# 15_LMS2_RF1_Misc.net
KiCad netlist of a schematic drawn in Altium Designer
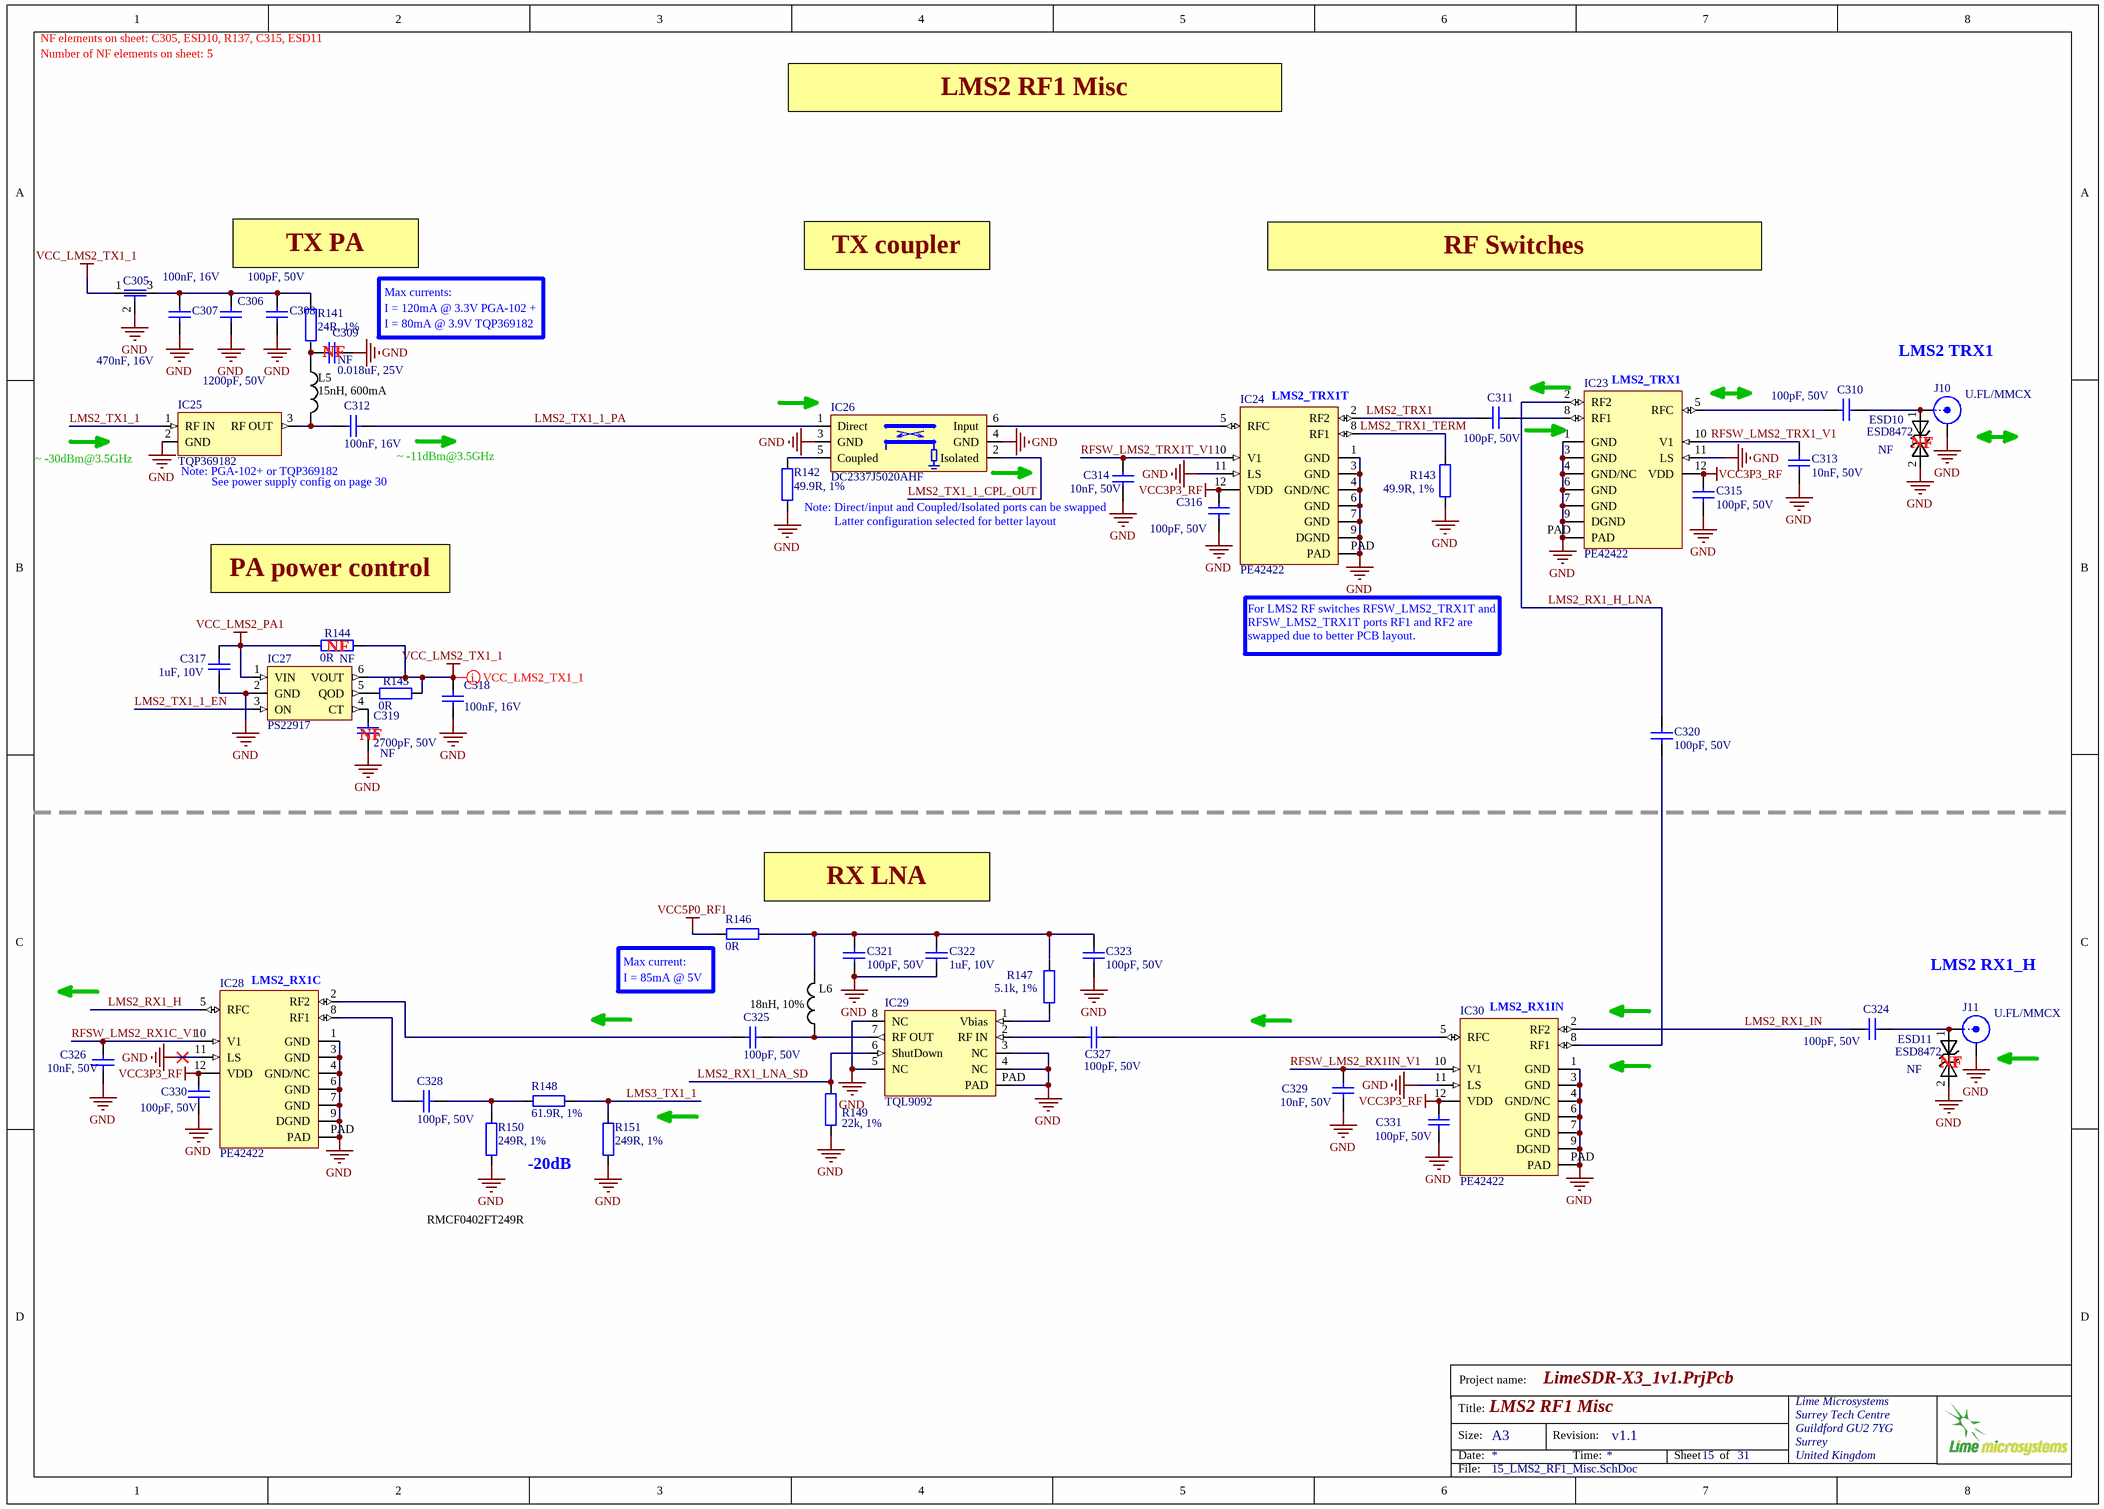
[diagram p0: 15_LMS2_RF1_Misc.SchDoc]

(export (version "E")
  (design (tool "Eeschema 10.0.6"))
  (components
    (comp (ref "C305")
      (value "470nF, 16V")
      (footprint "CAP0805_FEEDTHROUGH")
      (fields
        (field (name "MANUFACTURER") "Murata")
        (field (name "TOLERANCE") "20%")
        (field (name "VOLTAGE") "16V")
      )
      (libsource (lib "LimeMicroAltiumLib_schLib_r01") (part "Cap_feed_through"))
    )
    (comp (ref "C306")
      (value "1200pF, 50V")
      (footprint "CAP0402")
      (fields (field (name "MANUFACTURER") "Kemet") (field (name "TOLERANCE") "±5%"))
      (libsource (lib "") (part "Cap_0402_12"))
    )
    (comp (ref "C307")
      (value "100nF, 16V")
      (footprint "CAP0402")
      (fields (field (name "MANUFACTURER") "Murata Electronics") (field (name "TOLERANCE") "10 %"))
      (libsource (lib "") (part "Cap_0402_10"))
    )
    (comp (ref "C308")
      (value "100pF, 50V")
      (footprint "CAP0402")
      (fields (field (name "TOLERANCE") "±5%") (field (name "MANUFACTURER") "Yageo"))
      (libsource (lib "") (part "Cap_0402_10"))
    )
    (comp (ref "C309")
      (value "0.018uF, 25V")
      (footprint "CAP0402")
      (fields
        (field (name "ASSEMBLY INFO") "NF")
        (field (name "MANUFACTURER") "Yageo")
        (field (name "TOLERANCE") "10%")
      )
      (libsource (lib "") (part "Cap_0402_5"))
    )
    (comp (ref "C310")
      (value "100pF, 50V")
      (footprint "CAP0402")
      (fields (field (name "TOLERANCE") "±5%") (field (name "MANUFACTURER") "Yageo"))
      (libsource (lib "") (part "Cap_0402_3"))
    )
    (comp (ref "C311")
      (value "100pF, 50V")
      (footprint "CAP0402")
      (fields (field (name "TOLERANCE") "±5%") (field (name "MANUFACTURER") "Yageo"))
      (libsource (lib "") (part "Cap_0402_3"))
    )
    (comp (ref "C312")
      (value "100nF, 16V")
      (footprint "CAP0402")
      (fields (field (name "MANUFACTURER") "Murata Electronics") (field (name "TOLERANCE") "10 %"))
      (libsource (lib "") (part "Cap_0402_1"))
    )
    (comp (ref "C313")
      (value "10nF, 50V")
      (footprint "CAP0402")
      (fields
        (field (name "MANUFACTURER") "Murata Electronics North America")
        (field (name "TOLERANCE") "±10%")
      )
      (libsource (lib "") (part "Cap_0402_7"))
    )
    (comp (ref "C314")
      (value "10nF, 50V")
      (footprint "CAP0402")
      (fields
        (field (name "MANUFACTURER") "Murata Electronics North America")
        (field (name "TOLERANCE") "±10%")
      )
      (libsource (lib "") (part "Cap_0402_7"))
    )
    (comp (ref "C315")
      (value "100pF, 50V")
      (footprint "CAP0402")
      (fields (field (name "TOLERANCE") "±5%") (field (name "MANUFACTURER") "Yageo"))
      (libsource (lib "LimeMicroAltiumLib_schLib") (part "Cap_0402"))
    )
    (comp (ref "C316")
      (value "100pF, 50V")
      (footprint "CAP0402")
      (fields (field (name "TOLERANCE") "±5%") (field (name "MANUFACTURER") "Yageo"))
      (libsource (lib "LimeMicroAltiumLib_schLib") (part "Cap_0402"))
    )
    (comp (ref "C317")
      (value "1uF, 10V")
      (footprint "CAP0402")
      (fields (field (name "MANUFACTURER") "TDK"))
      (libsource (lib "") (part "Cap_0402_2"))
    )
    (comp (ref "C318")
      (value "100nF, 16V")
      (footprint "CAP0402")
      (fields (field (name "MANUFACTURER") "Murata Electronics") (field (name "TOLERANCE") "10 %"))
      (libsource (lib "") (part "Cap_0402_2"))
    )
    (comp (ref "C319")
      (value "2700pF, 50V")
      (footprint "CAP0402")
      (fields
        (field (name "ASSEMBLY INFO") "NF")
        (field (name "TOLERANCE") "±10%")
        (field (name "MANUFACTURER") "Murata Electronics North America")
      )
      (libsource (lib "") (part "Cap_0402_10"))
    )
    (comp (ref "C320")
      (value "100pF, 50V")
      (footprint "CAP0402")
      (fields (field (name "TOLERANCE") "±5%") (field (name "MANUFACTURER") "Yageo"))
      (libsource (lib "") (part "Cap_0402_3"))
    )
    (comp (ref "C321")
      (value "100pF, 50V")
      (footprint "CAP0402")
      (fields (field (name "TOLERANCE") "±5%") (field (name "MANUFACTURER") "Yageo"))
      (libsource (lib "") (part "Cap_0402_8"))
    )
    (comp (ref "C322")
      (value "1uF, 10V")
      (footprint "CAP0402")
      (fields (field (name "MANUFACTURER") "TDK"))
      (libsource (lib "") (part "Cap_0402_11"))
    )
    (comp (ref "C323")
      (value "100pF, 50V")
      (footprint "CAP0402")
      (fields (field (name "TOLERANCE") "±5%") (field (name "MANUFACTURER") "Yageo"))
      (libsource (lib "") (part "Cap_0402_8"))
    )
    (comp (ref "C324")
      (value "100pF, 50V")
      (footprint "CAP0402")
      (fields (field (name "TOLERANCE") "±5%") (field (name "MANUFACTURER") "Yageo"))
      (libsource (lib "") (part "Cap_0402_3"))
    )
    (comp (ref "C325")
      (value "100pF, 50V")
      (footprint "CAP0402")
      (fields (field (name "TOLERANCE") "±5%") (field (name "MANUFACTURER") "Yageo"))
      (libsource (lib "") (part "Cap_0402_2"))
    )
    (comp (ref "C326")
      (value "10nF, 50V")
      (footprint "CAP0402")
      (fields
        (field (name "MANUFACTURER") "Murata Electronics North America")
        (field (name "TOLERANCE") "±10%")
      )
      (libsource (lib "") (part "Cap_0402_4"))
    )
    (comp (ref "C327")
      (value "100pF, 50V")
      (footprint "CAP0402")
      (fields (field (name "TOLERANCE") "±5%") (field (name "MANUFACTURER") "Yageo"))
      (libsource (lib "") (part "Cap_0402_6"))
    )
    (comp (ref "C328")
      (value "100pF, 50V")
      (footprint "CAP0402")
      (fields (field (name "TOLERANCE") "±5%") (field (name "MANUFACTURER") "Yageo"))
      (libsource (lib "") (part "Cap_0402_3"))
    )
    (comp (ref "C329")
      (value "10nF, 50V")
      (footprint "CAP0402")
      (fields
        (field (name "MANUFACTURER") "Murata Electronics North America")
        (field (name "TOLERANCE") "±10%")
      )
      (libsource (lib "") (part "Cap_0402_5"))
    )
    (comp (ref "C330")
      (value "100pF, 50V")
      (footprint "CAP0402")
      (fields (field (name "TOLERANCE") "±5%") (field (name "MANUFACTURER") "Yageo"))
      (libsource (lib "") (part "Cap_0402_9"))
    )
    (comp (ref "C331")
      (value "100pF, 50V")
      (footprint "CAP0402")
      (fields (field (name "TOLERANCE") "±5%") (field (name "MANUFACTURER") "Yageo"))
      (libsource (lib "") (part "Cap_0402_1"))
    )
    (comp (ref "ESD10")
      (value "ESD8472")
      (footprint "ESD8472_X3DFN2")
      (fields (field (name "MANUFACTURER") "ON Semiconductor") (field (name "ASSEMBLY INFO") "NF"))
      (libsource (lib "LimeMicroAltiumLib_schLib") (part "ESD8472"))
    )
    (comp (ref "ESD11")
      (value "ESD8472")
      (footprint "ESD8472_X3DFN2")
      (fields (field (name "MANUFACTURER") "ON Semiconductor") (field (name "ASSEMBLY INFO") "NF"))
      (libsource (lib "") (part "ESD8472_1"))
    )
    (comp (ref "IC23")
      (value "PE42422")
      (footprint "PE42422_QFN12")
      (fields (field (name "MANUFACTURER") "Peregrine Semiconductor"))
      (libsource (lib "") (part "PE42422_3"))
    )
    (comp (ref "IC24")
      (value "PE42422")
      (footprint "PE42422_QFN12")
      (fields (field (name "MANUFACTURER") "Peregrine Semiconductor"))
      (libsource (lib "LimeMicroAltiumLib_schLib") (part "PE42422"))
    )
    (comp (ref "IC25")
      (value "TQP369182")
      (footprint "PGA-102+_SOT89")
      (fields (field (name "MANUFACTURER") "Qorvo"))
      (libsource (lib "LimeMicroAltiumLib_schLib_r01") (part "PGA-102+_PA"))
    )
    (comp (ref "IC26")
      (value "DC2337J5020AHF")
      (footprint "DC2337J5020AHF_ANAREN_COUPLER_0805")
      (fields (field (name "MANUFACTURER") "Anaren"))
      (libsource (lib "LimeMicroAltiumLib_schLib_r02") (part "DC2337J5020AHF_coupler"))
    )
    (comp (ref "IC27")
      (value "PS22917")
      (footprint "SOT23-6")
      (fields (field (name "MANUFACTURER") "Texas Instruments"))
      (libsource (lib "LimeMicroAltiumLib_schLib") (part "TPS22918"))
    )
    (comp (ref "IC28")
      (value "PE42422")
      (footprint "PE42422_QFN12")
      (fields (field (name "MANUFACTURER") "Peregrine Semiconductor"))
      (libsource (lib "") (part "PE42422_1"))
    )
    (comp (ref "IC29")
      (value "TQL9092")
      (footprint "TQL9092")
      (fields (field (name "MANUFACTURER") "Qorvo"))
      (libsource (lib "LimeMicroAltiumLib_schLib") (part "TQL9092"))
    )
    (comp (ref "IC30")
      (value "PE42422")
      (footprint "PE42422_QFN12")
      (fields (field (name "MANUFACTURER") "Peregrine Semiconductor"))
      (libsource (lib "") (part "PE42422_2"))
    )
    (comp (ref "J10")
      (value "U.FL/MMCX")
      (footprint "MMCX_UFL_conn_m")
      (description "CONN UMC RCPT STR 50 OHM SMD")
      (fields (field (name "MANUFACTURER") "Amphenol RF"))
      (libsource (lib "LimeMicroAltiumLib_schLib") (part "RF_IF_connector"))
    )
    (comp (ref "J11")
      (value "U.FL/MMCX")
      (footprint "MMCX_UFL_conn_m")
      (description "CONN UMC RCPT STR 50 OHM SMD")
      (fields (field (name "MANUFACTURER") "Amphenol RF"))
      (libsource (lib "LimeMicroAltiumLib_schLib") (part "RF_IF_connector"))
    )
    (comp (ref "L5")
      (value "15nH, 600mA")
      (footprint "RES0805")
      (fields (field (name "MANUFACTURER") "Bourns") (field (name "TOLERANCE") "5%"))
      (libsource (lib "LimeMicroAltiumLib_schLib") (part "Inductor_0603"))
    )
    (comp (ref "L6")
      (value "18nH, 10%")
      (footprint "RES0603")
      (fields (field (name "MANUFACTURER") "Pulse Electronics Network") (field (name "TOLERANCE") "±10%"))
      (libsource (lib "LimeMicroAltiumLib_schLib") (part "Inductor"))
    )
    (comp (ref "R141")
      (value "24R, 1%")
      (footprint "RES0402")
      (fields (field (name "MANUFACTURER") "Yageo") (field (name "TOLERANCE") "1%"))
      (libsource (lib "LimeFPGAboard_schLib") (part "Res_0402"))
    )
    (comp (ref "R142")
      (value "49.9R, 1%")
      (footprint "RES0402")
      (fields
        (field (name "TOLERANCE") "±1%")
        (field (name "MANUFACTURER") "Samsung Electro-Mechanics America, Inc.")
        (field (name "MANUFACTURER PART NUMBER") "RC1005F49R9CS")
      )
      (libsource (lib "LimeMicroAltiumLib_schLib") (part "Res_0402"))
    )
    (comp (ref "R143")
      (value "49.9R, 1%")
      (footprint "RES0402")
      (fields
        (field (name "TOLERANCE") "±1%")
        (field (name "MANUFACTURER") "Samsung Electro-Mechanics America, Inc.")
        (field (name "MANUFACTURER PART NUMBER") "RC1005F49R9CS")
      )
      (libsource (lib "LimeMicroAltiumLib_schLib") (part "Res_0402"))
    )
    (comp (ref "R144")
      (value "0R")
      (footprint "RES0402")
      (fields
        (field (name "ASSEMBLY INFO") "NF")
        (field (name "MANUFACTURER") "Yageo")
        (field (name "TOLERANCE") "Jumper")
      )
      (libsource (lib "") (part "Res_0402_1"))
    )
    (comp (ref "R145")
      (value "0R")
      (footprint "RES0402")
      (fields (field (name "MANUFACTURER") "Yageo") (field (name "TOLERANCE") "Jumper"))
      (libsource (lib "") (part "Res_0402_1"))
    )
    (comp (ref "R146")
      (value "0R")
      (footprint "RES0402")
      (fields (field (name "MANUFACTURER") "Yageo") (field (name "TOLERANCE") "Jumper"))
      (libsource (lib "LimeMicroAltiumLib_schLib") (part "Res_0402"))
    )
    (comp (ref "R147")
      (value "5.1k, 1%")
      (footprint "RES0603")
      (fields (field (name "MANUFACTURER") "Stackpole Electronics") (field (name "TOLERANCE") "1%"))
      (libsource (lib "LimeMicroAltiumLib_schLib") (part "Res_0603"))
    )
    (comp (ref "R148")
      (value "61.9R, 1%")
      (footprint "RES0402")
      (fields (field (name "MANUFACTURER") "Yageo") (field (name "TOLERANCE") "1%"))
      (libsource (lib "") (part "Res_0402_1"))
    )
    (comp (ref "R149")
      (value "22k, 1%")
      (footprint "RES0402")
      (fields (field (name "MANUFACTURER") "Yageo") (field (name "TOLERANCE") "±1%"))
      (libsource (lib "") (part "Res_0402_1"))
    )
    (comp (ref "R150")
      (value "249R, 1%")
      (footprint "RES0402")
      (fields (field (name "MANUFACTURER") "Stackpole Electronics Inc") (field (name "TOLERANCE") "±1%"))
      (libsource (lib "") (part "Res_0402_1"))
    )
    (comp (ref "R151")
      (value "249R, 1%")
      (footprint "RES0402")
      (fields (field (name "MANUFACTURER") "Stackpole Electronics Inc") (field (name "TOLERANCE") "±1%"))
      (libsource (lib "") (part "Res_0402_1"))
    )
  )
  (nets
    (net (code "1") (name "/LMS2_RX1_H") (class "Default")
      (node (ref "IC28") (pin "5") (pinfunction "RFC_5") (pintype "bidirectional"))
    )
    (net (code "2") (name "/LMS2_RX1_H_LNA") (class "Default")
      (node (ref "C320") (pin "2") (pinfunction "2_2") (pintype "passive"))
      (node (ref "IC23") (pin "2") (pinfunction "RF2_2") (pintype "bidirectional"))
    )
    (net (code "3") (name "/LMS2_RX1_IN") (class "Default")
      (node (ref "C324") (pin "1") (pinfunction "1_1") (pintype "passive"))
      (node (ref "IC30") (pin "2") (pinfunction "RF2_2") (pintype "bidirectional"))
    )
    (net (code "4") (name "/LMS2_RX1_LNA_SD") (class "Default")
      (node (ref "IC29") (pin "6") (pinfunction "ShutDown_6") (pintype "input"))
      (node (ref "R149") (pin "2") (pinfunction "2_2") (pintype "passive"))
    )
    (net (code "5") (name "/LMS2_TRX1") (class "Default")
      (node (ref "C311") (pin "1") (pinfunction "1_1") (pintype "passive"))
      (node (ref "IC24") (pin "2") (pinfunction "RF2_2") (pintype "bidirectional"))
    )
    (net (code "6") (name "/LMS2_TRX1_TERM") (class "Default")
      (node (ref "IC24") (pin "8") (pinfunction "RF1_8") (pintype "bidirectional"))
      (node (ref "R143") (pin "1") (pinfunction "1_1") (pintype "passive"))
    )
    (net (code "7") (name "/LMS2_TX1_1") (class "Default")
      (node (ref "IC25") (pin "1") (pinfunction "RF_IN_1") (pintype "input"))
    )
    (net (code "8") (name "/LMS2_TX1_1_CPL_OUT") (class "Default")
      (node (ref "IC26") (pin "2") (pinfunction "Isolated_2") (pintype "passive"))
    )
    (net (code "9") (name "/LMS2_TX1_1_EN") (class "Default")
      (node (ref "IC27") (pin "3") (pinfunction "ON_3") (pintype "input"))
    )
    (net (code "10") (name "/LMS2_TX1_1_PA") (class "Default")
      (node (ref "C312") (pin "1") (pinfunction "1_1") (pintype "passive"))
      (node (ref "IC26") (pin "1") (pinfunction "Direct_1") (pintype "passive"))
    )
    (net (code "11") (name "/LMS3_TX1_1") (class "Default")
      (node (ref "R148") (pin "2") (pinfunction "2_2") (pintype "passive"))
      (node (ref "R151") (pin "2") (pinfunction "2_2") (pintype "passive"))
    )
    (net (code "12") (name "/RFSW_LMS2_RX1C_V1") (class "Default")
      (node (ref "C326") (pin "1") (pinfunction "1_1") (pintype "passive"))
      (node (ref "IC28") (pin "10") (pinfunction "V1_10") (pintype "input"))
    )
    (net (code "13") (name "/RFSW_LMS2_RX1IN_V1") (class "Default")
      (node (ref "C329") (pin "1") (pinfunction "1_1") (pintype "passive"))
      (node (ref "IC30") (pin "10") (pinfunction "V1_10") (pintype "input"))
    )
    (net (code "14") (name "/RFSW_LMS2_TRX1T_V1") (class "Default")
      (node (ref "C314") (pin "1") (pinfunction "1_1") (pintype "passive"))
      (node (ref "IC24") (pin "10") (pinfunction "V1_10") (pintype "input"))
    )
    (net (code "15") (name "/RFSW_LMS2_TRX1_V1") (class "Default")
      (node (ref "C313") (pin "1") (pinfunction "1_1") (pintype "passive"))
      (node (ref "IC23") (pin "10") (pinfunction "V1_10") (pintype "input"))
    )
    (net (code "16") (name "GND") (class "Default")
      (node (ref "C305") (pin "2") (pinfunction "2_2") (pintype "passive"))
      (node (ref "C306") (pin "2") (pinfunction "2_2") (pintype "passive"))
      (node (ref "C307") (pin "1") (pinfunction "1_1") (pintype "passive"))
      (node (ref "C308") (pin "2") (pinfunction "2_2") (pintype "passive"))
      (node (ref "C309") (pin "2") (pinfunction "2_2") (pintype "passive"))
      (node (ref "C313") (pin "2") (pinfunction "2_2") (pintype "passive"))
      (node (ref "C314") (pin "2") (pinfunction "2_2") (pintype "passive"))
      (node (ref "C315") (pin "1") (pinfunction "1_1") (pintype "passive"))
      (node (ref "C316") (pin "1") (pinfunction "1_1") (pintype "passive"))
      (node (ref "C317") (pin "1") (pinfunction "1_1") (pintype "passive"))
      (node (ref "C318") (pin "1") (pinfunction "1_1") (pintype "passive"))
      (node (ref "C319") (pin "2") (pinfunction "2_2") (pintype "passive"))
      (node (ref "C321") (pin "2") (pinfunction "2_2") (pintype "passive"))
      (node (ref "C322") (pin "1") (pinfunction "1_1") (pintype "passive"))
      (node (ref "C323") (pin "2") (pinfunction "2_2") (pintype "passive"))
      (node (ref "C326") (pin "2") (pinfunction "2_2") (pintype "passive"))
      (node (ref "C329") (pin "2") (pinfunction "2_2") (pintype "passive"))
      (node (ref "C330") (pin "1") (pinfunction "1_1") (pintype "passive"))
      (node (ref "C331") (pin "1") (pinfunction "1_1") (pintype "passive"))
      (node (ref "ESD10") (pin "2") (pinfunction "2_2") (pintype "passive"))
      (node (ref "ESD11") (pin "2") (pinfunction "2_2") (pintype "passive"))
      (node (ref "IC23") (pin "1") (pinfunction "GND_1") (pintype "passive"))
      (node (ref "IC23") (pin "11") (pinfunction "LS_11") (pintype "input"))
      (node (ref "IC23") (pin "3") (pinfunction "GND_3") (pintype "passive"))
      (node (ref "IC23") (pin "4") (pinfunction "GND/NC_4") (pintype "passive"))
      (node (ref "IC23") (pin "6") (pinfunction "GND_6") (pintype "passive"))
      (node (ref "IC23") (pin "7") (pinfunction "GND_7") (pintype "passive"))
      (node (ref "IC23") (pin "9") (pinfunction "DGND_9") (pintype "passive"))
      (node (ref "IC23") (pin "PAD") (pinfunction "PAD_PAD") (pintype "passive"))
      (node (ref "IC24") (pin "1") (pinfunction "GND_1") (pintype "passive"))
      (node (ref "IC24") (pin "11") (pinfunction "LS_11") (pintype "input"))
      (node (ref "IC24") (pin "3") (pinfunction "GND_3") (pintype "passive"))
      (node (ref "IC24") (pin "4") (pinfunction "GND/NC_4") (pintype "passive"))
      (node (ref "IC24") (pin "6") (pinfunction "GND_6") (pintype "passive"))
      (node (ref "IC24") (pin "7") (pinfunction "GND_7") (pintype "passive"))
      (node (ref "IC24") (pin "9") (pinfunction "DGND_9") (pintype "passive"))
      (node (ref "IC24") (pin "PAD") (pinfunction "PAD_PAD") (pintype "passive"))
      (node (ref "IC25") (pin "2") (pinfunction "GND_2") (pintype "passive"))
      (node (ref "IC26") (pin "3") (pinfunction "GND_3") (pintype "passive"))
      (node (ref "IC26") (pin "4") (pinfunction "GND_4") (pintype "passive"))
      (node (ref "IC27") (pin "2") (pinfunction "GND_2") (pintype "passive"))
      (node (ref "IC28") (pin "1") (pinfunction "GND_1") (pintype "passive"))
      (node (ref "IC28") (pin "11") (pinfunction "LS_11") (pintype "input"))
      (node (ref "IC28") (pin "3") (pinfunction "GND_3") (pintype "passive"))
      (node (ref "IC28") (pin "4") (pinfunction "GND/NC_4") (pintype "passive"))
      (node (ref "IC28") (pin "6") (pinfunction "GND_6") (pintype "passive"))
      (node (ref "IC28") (pin "7") (pinfunction "GND_7") (pintype "passive"))
      (node (ref "IC28") (pin "9") (pinfunction "DGND_9") (pintype "passive"))
      (node (ref "IC28") (pin "PAD") (pinfunction "PAD_PAD") (pintype "passive"))
      (node (ref "IC29") (pin "3") (pinfunction "NC_3") (pintype "passive"))
      (node (ref "IC29") (pin "4") (pinfunction "NC_4") (pintype "passive"))
      (node (ref "IC29") (pin "5") (pinfunction "NC_5") (pintype "passive"))
      (node (ref "IC29") (pin "8") (pinfunction "NC_8") (pintype "passive"))
      (node (ref "IC29") (pin "PAD") (pinfunction "PAD_PAD") (pintype "passive"))
      (node (ref "IC30") (pin "1") (pinfunction "GND_1") (pintype "passive"))
      (node (ref "IC30") (pin "11") (pinfunction "LS_11") (pintype "input"))
      (node (ref "IC30") (pin "3") (pinfunction "GND_3") (pintype "passive"))
      (node (ref "IC30") (pin "4") (pinfunction "GND/NC_4") (pintype "passive"))
      (node (ref "IC30") (pin "6") (pinfunction "GND_6") (pintype "passive"))
      (node (ref "IC30") (pin "7") (pinfunction "GND_7") (pintype "passive"))
      (node (ref "IC30") (pin "9") (pinfunction "DGND_9") (pintype "passive"))
      (node (ref "IC30") (pin "PAD") (pinfunction "PAD_PAD") (pintype "passive"))
      (node (ref "J10") (pin "2") (pinfunction "Y_2") (pintype "passive"))
      (node (ref "J11") (pin "2") (pinfunction "Y_2") (pintype "passive"))
      (node (ref "R142") (pin "2") (pinfunction "2_2") (pintype "passive"))
      (node (ref "R143") (pin "2") (pinfunction "2_2") (pintype "passive"))
      (node (ref "R149") (pin "1") (pinfunction "1_1") (pintype "passive"))
      (node (ref "R150") (pin "1") (pinfunction "1_1") (pintype "passive"))
      (node (ref "R151") (pin "1") (pinfunction "1_1") (pintype "passive"))
    )
    (net (code "17") (name "Net-(C305-Pad3)") (class "Default")
      (node (ref "C305") (pin "3") (pinfunction "3_3") (pintype "passive"))
      (node (ref "C306") (pin "1") (pinfunction "1_1") (pintype "passive"))
      (node (ref "C307") (pin "2") (pinfunction "2_2") (pintype "passive"))
      (node (ref "C308") (pin "1") (pinfunction "1_1") (pintype "passive"))
      (node (ref "R141") (pin "1") (pinfunction "1_1") (pintype "passive"))
    )
    (net (code "18") (name "Net-(C309-Pad1)") (class "Default")
      (node (ref "C309") (pin "1") (pinfunction "1_1") (pintype "passive"))
      (node (ref "L5") (pin "1") (pinfunction "1_1") (pintype "passive"))
      (node (ref "R141") (pin "2") (pinfunction "2_2") (pintype "passive"))
    )
    (net (code "19") (name "Net-(C321-Pad1)") (class "Default")
      (node (ref "C321") (pin "1") (pinfunction "1_1") (pintype "passive"))
      (node (ref "C322") (pin "2") (pinfunction "2_2") (pintype "passive"))
      (node (ref "C323") (pin "1") (pinfunction "1_1") (pintype "passive"))
      (node (ref "L6") (pin "1") (pinfunction "1_1") (pintype "passive"))
      (node (ref "R146") (pin "2") (pinfunction "2_2") (pintype "passive"))
      (node (ref "R147") (pin "2") (pinfunction "2_2") (pintype "passive"))
    )
    (net (code "20") (name "Net-(C328-Pad1)") (class "Default")
      (node (ref "C328") (pin "1") (pinfunction "1_1") (pintype "passive"))
      (node (ref "R148") (pin "1") (pinfunction "1_1") (pintype "passive"))
      (node (ref "R150") (pin "2") (pinfunction "2_2") (pintype "passive"))
    )
    (net (code "21") (name "Net-(IC23-RF1)") (class "Default")
      (node (ref "C311") (pin "2") (pinfunction "2_2") (pintype "passive"))
      (node (ref "IC23") (pin "8") (pinfunction "RF1_8") (pintype "bidirectional"))
    )
    (net (code "22") (name "Net-(IC23-RFC)") (class "Default")
      (node (ref "C310") (pin "1") (pinfunction "1_1") (pintype "passive"))
      (node (ref "IC23") (pin "5") (pinfunction "RFC_5") (pintype "bidirectional"))
    )
    (net (code "23") (name "Net-(IC24-RFC)") (class "Default")
      (node (ref "IC24") (pin "5") (pinfunction "RFC_5") (pintype "bidirectional"))
      (node (ref "IC26") (pin "6") (pinfunction "Input_6") (pintype "passive"))
    )
    (net (code "24") (name "Net-(IC25-RF_OUT)") (class "Default")
      (node (ref "C312") (pin "2") (pinfunction "2_2") (pintype "passive"))
      (node (ref "IC25") (pin "3") (pinfunction "RF_OUT_3") (pintype "output"))
      (node (ref "L5") (pin "2") (pinfunction "2_2") (pintype "passive"))
    )
    (net (code "25") (name "Net-(IC26-Coupled)") (class "Default")
      (node (ref "IC26") (pin "5") (pinfunction "Coupled_5") (pintype "passive"))
      (node (ref "R142") (pin "1") (pinfunction "1_1") (pintype "passive"))
    )
    (net (code "26") (name "Net-(IC27-CT)") (class "Default")
      (node (ref "C319") (pin "1") (pinfunction "1_1") (pintype "passive"))
      (node (ref "IC27") (pin "4") (pinfunction "CT_4") (pintype "output"))
    )
    (net (code "27") (name "Net-(IC27-QOD)") (class "Default")
      (node (ref "IC27") (pin "5") (pinfunction "QOD_5") (pintype "output"))
      (node (ref "R145") (pin "2") (pinfunction "2_2") (pintype "passive"))
    )
    (net (code "28") (name "Net-(IC28-RF1)") (class "Default")
      (node (ref "C328") (pin "2") (pinfunction "2_2") (pintype "passive"))
      (node (ref "IC28") (pin "8") (pinfunction "RF1_8") (pintype "bidirectional"))
    )
    (net (code "29") (name "Net-(IC28-RF2)") (class "Default")
      (node (ref "C325") (pin "1") (pinfunction "1_1") (pintype "passive"))
      (node (ref "IC28") (pin "2") (pinfunction "RF2_2") (pintype "bidirectional"))
    )
    (net (code "30") (name "Net-(IC29-RF_IN)") (class "Default")
      (node (ref "C327") (pin "1") (pinfunction "1_1") (pintype "passive"))
      (node (ref "IC29") (pin "2") (pinfunction "RF_IN_2") (pintype "input"))
    )
    (net (code "31") (name "Net-(IC29-RF_OUT)") (class "Default")
      (node (ref "C325") (pin "2") (pinfunction "2_2") (pintype "passive"))
      (node (ref "IC29") (pin "7") (pinfunction "RF_OUT_7") (pintype "output"))
      (node (ref "L6") (pin "2") (pinfunction "2_2") (pintype "passive"))
    )
    (net (code "32") (name "Net-(IC29-Vbias)") (class "Default")
      (node (ref "IC29") (pin "1") (pinfunction "Vbias_1") (pintype "input"))
      (node (ref "R147") (pin "1") (pinfunction "1_1") (pintype "passive"))
    )
    (net (code "33") (name "Net-(IC30-RF1)") (class "Default")
      (node (ref "C320") (pin "1") (pinfunction "1_1") (pintype "passive"))
      (node (ref "IC30") (pin "8") (pinfunction "RF1_8") (pintype "bidirectional"))
    )
    (net (code "34") (name "Net-(IC30-RFC)") (class "Default")
      (node (ref "C327") (pin "2") (pinfunction "2_2") (pintype "passive"))
      (node (ref "IC30") (pin "5") (pinfunction "RFC_5") (pintype "bidirectional"))
    )
    (net (code "35") (name "Net-(J10-X)") (class "Default")
      (node (ref "C310") (pin "2") (pinfunction "2_2") (pintype "passive"))
      (node (ref "ESD10") (pin "1") (pinfunction "1_1") (pintype "passive"))
      (node (ref "J10") (pin "1") (pinfunction "X_1") (pintype "passive"))
    )
    (net (code "36") (name "Net-(J11-X)") (class "Default")
      (node (ref "C324") (pin "2") (pinfunction "2_2") (pintype "passive"))
      (node (ref "ESD11") (pin "1") (pinfunction "1_1") (pintype "passive"))
      (node (ref "J11") (pin "1") (pinfunction "X_1") (pintype "passive"))
    )
    (net (code "37") (name "VCC3P3_RF") (class "Default")
      (node (ref "C315") (pin "2") (pinfunction "2_2") (pintype "passive"))
      (node (ref "C316") (pin "2") (pinfunction "2_2") (pintype "passive"))
      (node (ref "C330") (pin "2") (pinfunction "2_2") (pintype "passive"))
      (node (ref "C331") (pin "2") (pinfunction "2_2") (pintype "passive"))
      (node (ref "IC23") (pin "12") (pinfunction "VDD_12") (pintype "power_in"))
      (node (ref "IC24") (pin "12") (pinfunction "VDD_12") (pintype "power_in"))
      (node (ref "IC28") (pin "12") (pinfunction "VDD_12") (pintype "power_in"))
      (node (ref "IC30") (pin "12") (pinfunction "VDD_12") (pintype "power_in"))
    )
    (net (code "38") (name "VCC5P0_RF1") (class "Default")
      (node (ref "R146") (pin "1") (pinfunction "1_1") (pintype "passive"))
    )
    (net (code "39") (name "VCC_LMS2_PA1") (class "Default")
      (node (ref "C317") (pin "2") (pinfunction "2_2") (pintype "passive"))
      (node (ref "IC27") (pin "1") (pinfunction "VIN_1") (pintype "input"))
      (node (ref "R144") (pin "2") (pinfunction "2_2") (pintype "passive"))
    )
    (net (code "40") (name "VCC_LMS2_TX1_1") (class "Default")
      (node (ref "C305") (pin "1") (pinfunction "1_1") (pintype "passive"))
      (node (ref "C318") (pin "2") (pinfunction "2_2") (pintype "passive"))
      (node (ref "IC27") (pin "6") (pinfunction "VOUT_6") (pintype "output"))
      (node (ref "R144") (pin "1") (pinfunction "1_1") (pintype "passive"))
      (node (ref "R145") (pin "1") (pinfunction "1_1") (pintype "passive"))
    )
  )
)
